# volt_boost.net
KiCad netlist of a schematic drawn in EAGLE
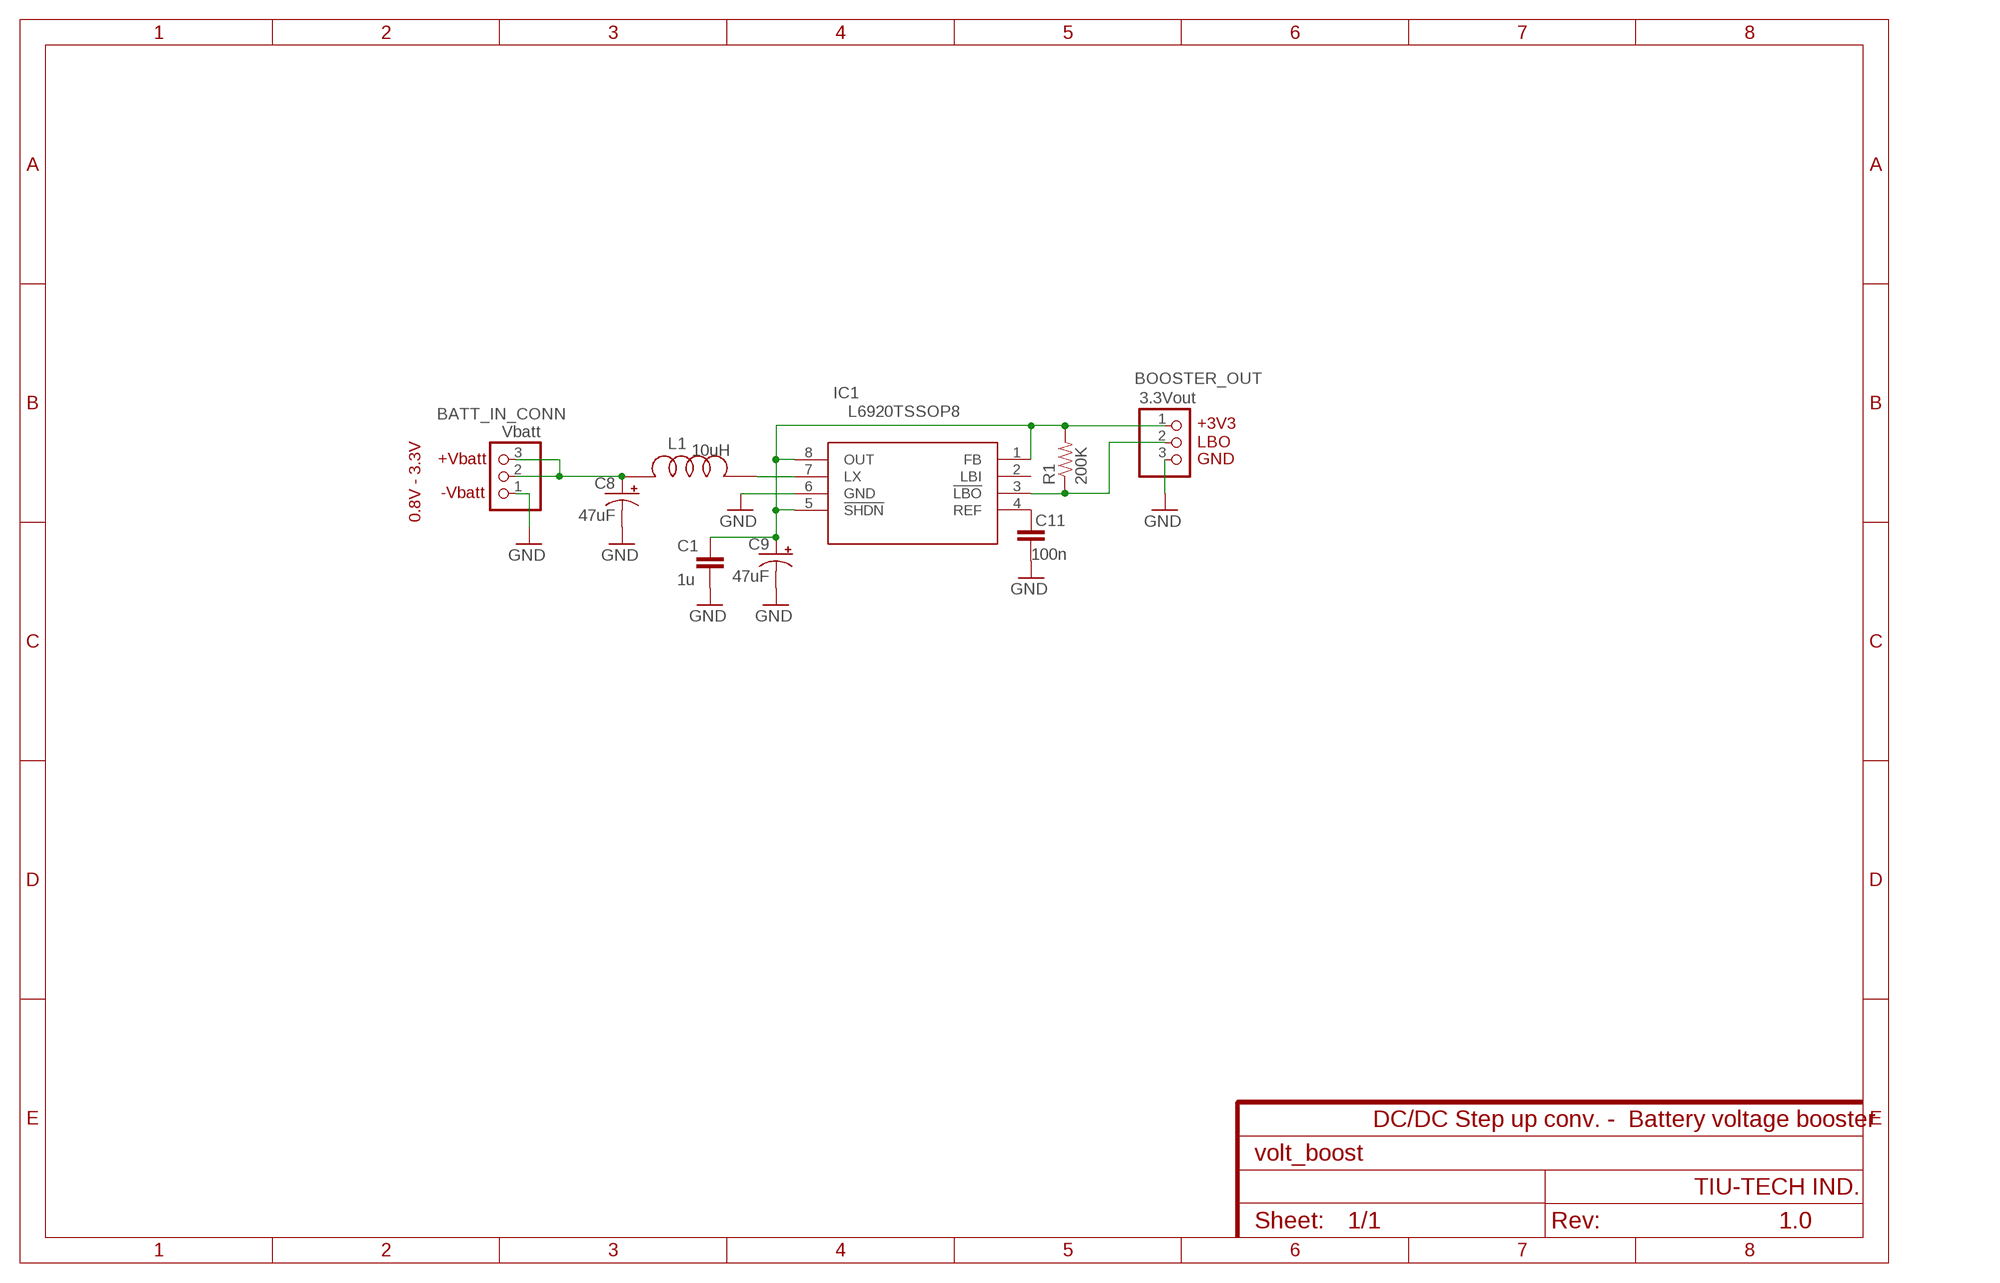
[diagram p0: schematic, sheet 1]

(export (version "E")
  (design (tool "Eeschema 10.0.6"))
  (components
    (comp (ref "BATT_IN_CONN")
      (value "Vbatt")
      (footprint "eagle-import:1X03")
      (libsource (lib "eagle-import") (part "PINHD-1X3"))
    )
    (comp (ref "BOOSTER_OUT")
      (value "3.3Vout")
      (footprint "eagle-import:1X03")
      (libsource (lib "eagle-import") (part "PINHD-1X3"))
    )
    (comp (ref "C1")
      (value "1u")
      (footprint "eagle-import:0805")
      (libsource (lib "eagle-import") (part "CAP0805"))
    )
    (comp (ref "C8")
      (value "47uF")
      (footprint "eagle-import:EIA3528")
      (libsource (lib "eagle-import") (part "47UF-TANT"))
    )
    (comp (ref "C9")
      (value "47uF")
      (footprint "eagle-import:EIA3528")
      (libsource (lib "eagle-import") (part "47UF-TANT"))
    )
    (comp (ref "C11")
      (value "100n")
      (footprint "eagle-import:0805")
      (libsource (lib "eagle-import") (part "CAP0805"))
    )
    (comp (ref "IC1")
      (value "L6920TSSOP8")
      (footprint "eagle-import:TSSOP8")
      (libsource (lib "eagle-import") (part "L6920TSSOP8"))
    )
    (comp (ref "L1")
      (value "10uH")
      (footprint "eagle-import:DLJ-4018")
      (libsource (lib "eagle-import") (part "DLJ-4018"))
    )
    (comp (ref "R1")
      (value "200K")
      (footprint "eagle-import:0805")
      (libsource (lib "eagle-import") (part "RESISTOR0805-RES"))
    )
  )
  (nets
    (net (code "1") (name "GND") (class "Default")
      (node (ref "BATT_IN_CONN") (pin "1") (pinfunction "1_1") (pintype "passive"))
      (node (ref "BOOSTER_OUT") (pin "3") (pinfunction "3_3") (pintype "passive"))
      (node (ref "C1") (pin "2") (pinfunction "2_2") (pintype "passive"))
      (node (ref "C11") (pin "2") (pinfunction "2_2") (pintype "passive"))
      (node (ref "C8") (pin "C") (pinfunction "-_C") (pintype "passive"))
      (node (ref "C9") (pin "C") (pinfunction "-_C") (pintype "passive"))
      (node (ref "IC1") (pin "6") (pinfunction "GND_6") (pintype "bidirectional"))
    )
    (net (code "2") (name "Net-(C8-+)") (class "Default")
      (node (ref "BATT_IN_CONN") (pin "2") (pinfunction "2_2") (pintype "passive"))
      (node (ref "BATT_IN_CONN") (pin "3") (pinfunction "3_3") (pintype "passive"))
      (node (ref "C8") (pin "A") (pinfunction "+_A") (pintype "passive"))
      (node (ref "L1") (pin "P$2") (pinfunction "2_P$2") (pintype "bidirectional"))
    )
    (net (code "3") (name "Net-(C9-+)") (class "Default")
      (node (ref "BOOSTER_OUT") (pin "1") (pinfunction "1_1") (pintype "passive"))
      (node (ref "C1") (pin "1") (pinfunction "1_1") (pintype "passive"))
      (node (ref "C9") (pin "A") (pinfunction "+_A") (pintype "passive"))
      (node (ref "IC1") (pin "1") (pinfunction "FB_1") (pintype "bidirectional"))
      (node (ref "IC1") (pin "5") (pinfunction "~{SHDN}_5") (pintype "bidirectional"))
      (node (ref "IC1") (pin "8") (pinfunction "OUT_8") (pintype "bidirectional"))
      (node (ref "R1") (pin "2") (pinfunction "2_2") (pintype "passive"))
    )
    (net (code "4") (name "Net-(IC1-LX)") (class "Default")
      (node (ref "IC1") (pin "7") (pinfunction "LX_7") (pintype "bidirectional"))
      (node (ref "L1") (pin "P$1") (pinfunction "1_P$1") (pintype "bidirectional"))
    )
    (net (code "5") (name "Net-(IC1-REF)") (class "Default")
      (node (ref "C11") (pin "1") (pinfunction "1_1") (pintype "passive"))
      (node (ref "IC1") (pin "4") (pinfunction "REF_4") (pintype "bidirectional"))
    )
    (net (code "6") (name "Net-(IC1-~{LBO})") (class "Default")
      (node (ref "BOOSTER_OUT") (pin "2") (pinfunction "2_2") (pintype "passive"))
      (node (ref "IC1") (pin "3") (pinfunction "~{LBO}_3") (pintype "bidirectional"))
      (node (ref "R1") (pin "1") (pinfunction "1_1") (pintype "passive"))
    )
    (net (code "7") (name "unconnected-(IC1-LBI-Pad2)") (class "Default")
      (node (ref "IC1") (pin "2") (pinfunction "LBI_2") (pintype "bidirectional"))
    )
  )
)
